# Power.net
KiCad netlist of a schematic drawn in Altium Designer
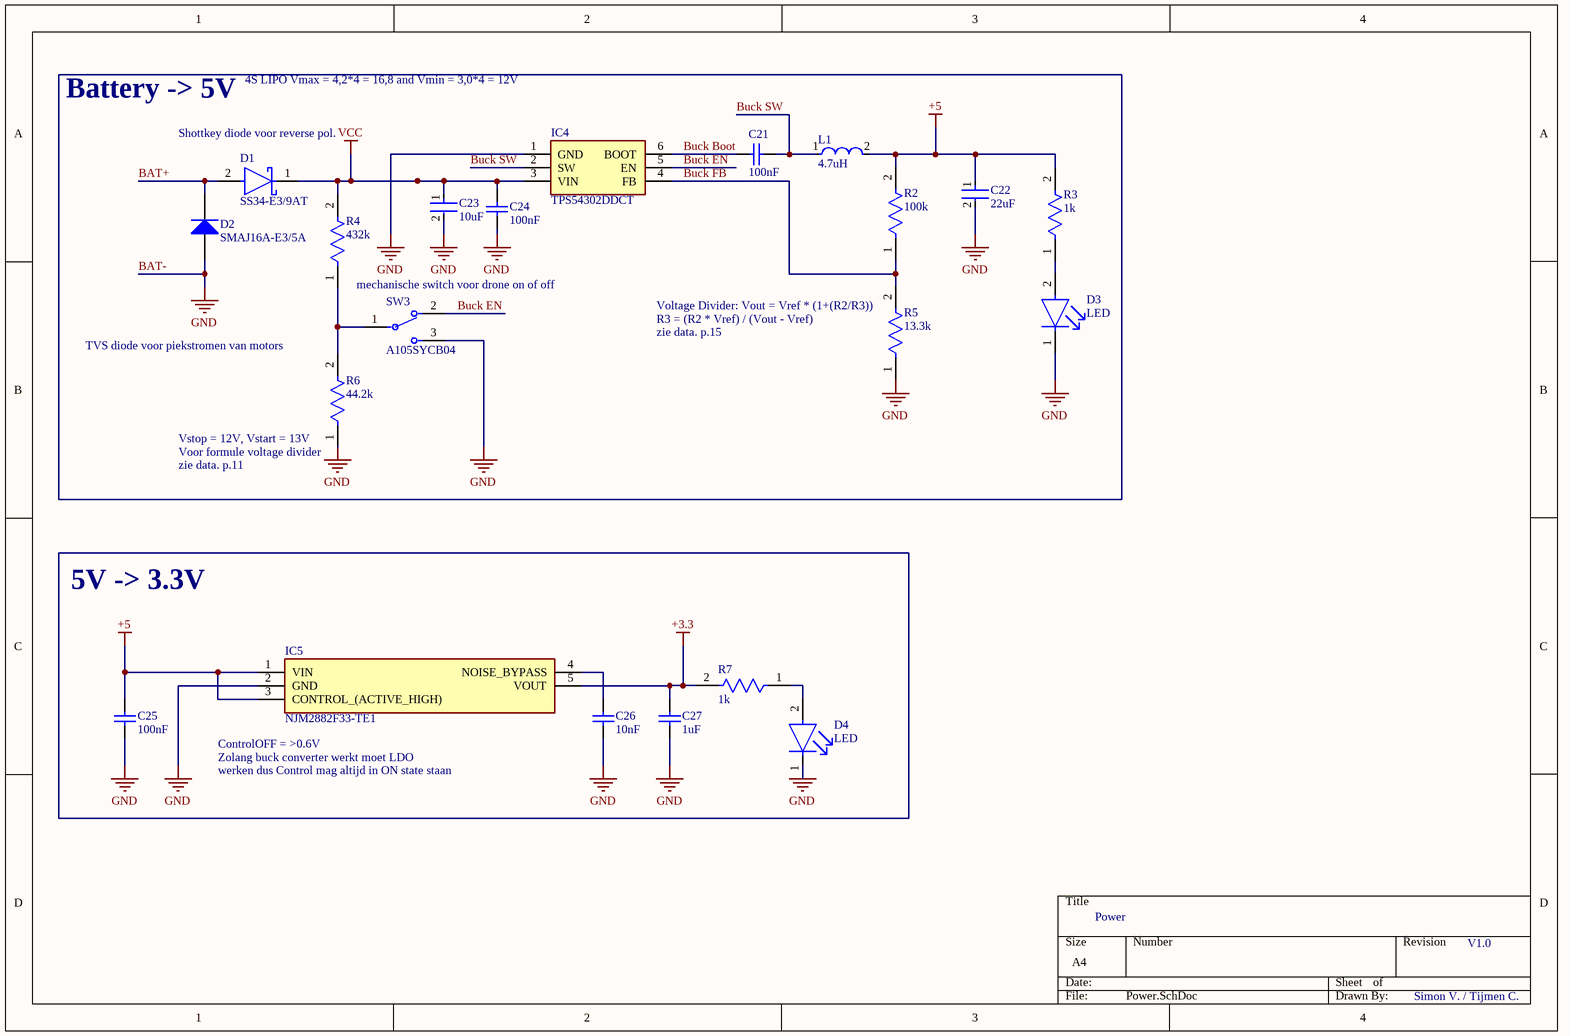
[diagram p0: Power.SchDoc]

(export (version "E")
  (design (tool "Eeschema 10.0.6"))
  (components
    (comp (ref "C21")
      (value "100nF")
      (footprint "CAPC1608X92X38ML15T08")
      (fields (field (name "PART NUMBER") "VJ0603Y104MXXAC") (field (name "MANUFACTURER") "Vitramon"))
      (libsource (lib "Altium Content Vault") (part "CAP"))
    )
    (comp (ref "C22")
      (value "22uF")
      (footprint "FP-GRM188-0_2-IPC_A")
      (description "Multilayer Ceramic Capacitor 22uF 20% 16V X5R 0603 Paper T/R")
      (libsource (lib "Altium Content Vault") (part "02cd4be3c70576c341d710602a673aa"))
    )
    (comp (ref "C23")
      (value "10uF")
      (footprint "FP-ZRB18AR61E106ME01L-MFG")
      (description "CAP CER 10UF 25V X5R 0603")
      (fields (field (name "VOLTAGE") "25V") (field (name "TOLERANCE") "20%"))
      (libsource (lib "Altium Content Vault") (part "b4654b650e69147ec39a6b967a45e02"))
    )
    (comp (ref "C24")
      (value "100nF")
      (footprint "CAPC1608X92X38ML15T08")
      (fields (field (name "PART NUMBER") "VJ0603Y104MXXAC") (field (name "MANUFACTURER") "Vitramon"))
      (libsource (lib "Altium Content Vault") (part "CAP"))
    )
    (comp (ref "C25")
      (value "100nF")
      (footprint "CAPC1608X92X38ML15T08")
      (fields (field (name "PART NUMBER") "VJ0603Y104MXXAC") (field (name "MANUFACTURER") "Vitramon"))
      (libsource (lib "Altium Content Vault") (part "CAP"))
    )
    (comp (ref "C26")
      (value "10nF")
      (footprint "CAPC1608X92X38LL15T08")
      (fields (field (name "MANUFACTURER") "Vitramon") (field (name "PART NUMBER") "VJ0603Y103JXXAC"))
      (libsource (lib "Altium Content Vault") (part "CAP"))
    )
    (comp (ref "C27")
      (value "1uF")
      (footprint "CAPC1608X90X35NL15T15")
      (fields
        (field (name "PART NUMBER") "0603YD105MAT2A")
        (field (name "MANUFACTURER") "AVX Interconnect / Elco")
      )
      (libsource (lib "Altium Content Vault") (part "CAP"))
    )
    (comp (ref "D1")
      (value "SS34-E3/9AT")
      (footprint "FP-SMC-MFG")
      (description "DIODE SCHOTTKY 40V 3A DO214AB")
      (libsource (lib "Altium Content Vault") (part "c1678fac7984e62e0809fbf79c06691"))
    )
    (comp (ref "D2")
      (value "SMAJ16A-E3/5A")
      (footprint "VISH-DO-214AC-2_M")
      (fields (field (name "MANUFACTURER") "Vishay Semiconductor"))
      (libsource (lib "Altium Content Vault") (part "VISH-K1A2-2"))
    )
    (comp (ref "D3")
      (value "LED")
      (footprint "FP-APHD1608LZGCK-MFG")
      (description "LED GREEN CLEAR 1608 SMD, type: APHD1608LZGCK")
      (libsource (lib "Altium Content Vault") (part "8706943c75ba83719d021d2fdc84c58"))
    )
    (comp (ref "D4")
      (value "LED")
      (footprint "FP-APHD1608LZGCK-MFG")
      (description "LED GREEN CLEAR 1608 SMD, type: APHD1608LZGCK")
      (libsource (lib "Altium Content Vault") (part "8706943c75ba83719d021d2fdc84c58"))
    )
    (comp (ref "IC4")
      (value "TPS54302DDCT")
      (footprint "SamacSys:SOT95P280X110-6N")
      (description "Integrated Circuit")
      (fields (field (name "MOUSER PART NUMBER") "595-TPS54302DDCT"))
      (libsource (lib "*") (part "TPS54302DDCT"))
    )
    (comp (ref "IC5")
      (value "NJM2882F33-TE1")
      (footprint "SamacSys:SOT95P280X130-5N")
      (description "Integrated Circuit")
      (fields (field (name "MOUSER PART NUMBER") "513-NJM2882F33-TE1"))
      (libsource (lib "*") (part "NJM2882F33-TE1"))
    )
    (comp (ref "L1")
      (value "4.7uH")
      (footprint "FP-IHLP-2020BZ-FP_1_905x2-MFG")
      (description "Fixed Inductors Commercial High Saturation Series 4.7uH 2.8A 116.6mΩ 20%")
      (fields (field (name "TOLERANCE") "20%"))
      (libsource (lib "Altium Content Vault") (part "725321dda6339637d4d059423bc1c3c"))
    )
    (comp (ref "R2")
      (value "100k")
      (footprint "FP-SR0603-MFG")
      (description "RES SMD 0603 1/4W 1% 100K OHM")
      (fields
        (field (name "OCTOPART") "https://octopart.com/sr0603fr-7t100kl-yageo-91478071")
        (field (name "TOLERANCE") "0.01")
      )
      (libsource (lib "Altium Content Vault") (part "1029c3af85768c4190bb7ad29bc67b5"))
    )
    (comp (ref "R3")
      (value "1k")
      (footprint "FP-AC0603-IPC_B")
      (description "RES 1kΩ 1.00% 0.2W 0603")
      (libsource (lib "Altium Content Vault") (part "1029c3af85768c4190bb7ad29bc67b5"))
    )
    (comp (ref "R4")
      (value "432k")
      (footprint "FP-AC0603-MFG")
      (description "RES 432KΩ 1.00% 0.1W 0603")
      (fields (field (name "TOLERANCE") "1%"))
      (libsource (lib "Altium Content Vault") (part "1029c3af85768c4190bb7ad29bc67b5"))
    )
    (comp (ref "R5")
      (value "13.3k")
      (footprint "FP-AF0603-IPC_A")
      (description "Anti-Sulfurated Chip Resistors Automotive Grade 13.3kΩ 1% 100ppm/°C 0603")
      (fields (field (name "TOLERANCE") "1%"))
      (libsource (lib "Altium Content Vault") (part "1029c3af85768c4190bb7ad29bc67b5"))
    )
    (comp (ref "R6")
      (value "44.2k")
      (footprint "FP-CRCW0603-HPe3-IPC_A")
      (description "RES Thick Film, 44.2kΩ, 1%, 0.33W, 100ppm/°C, 0603")
      (fields (field (name "TOLERANCE") "1%"))
      (libsource (lib "Altium Content Vault") (part "1029c3af85768c4190bb7ad29bc67b5"))
    )
    (comp (ref "R7")
      (value "1k")
      (footprint "FP-AC0603-IPC_B")
      (description "RES 1kΩ 1.00% 0.2W 0603")
      (libsource (lib "Altium Content Vault") (part "1029c3af85768c4190bb7ad29bc67b5"))
    )
    (comp (ref "SW3")
      (value "A105SYCB04")
      (footprint "FP-A105SYCB04-MFG")
      (description "SWITCH TOGGLE SPDT 0.4VA 20V")
      (libsource (lib "Altium Content Vault") (part "edb4360d59316bed191fd4b931ffec7"))
    )
  )
  (nets
    (net (code "1") (name "+3.3") (class "Default")
      (node (ref "C27") (pin "2") (pinfunction "2_2") (pintype "passive"))
      (node (ref "IC5") (pin "5") (pinfunction "VOUT_5") (pintype "passive"))
      (node (ref "R7") (pin "2") (pinfunction "2_2") (pintype "passive"))
    )
    (net (code "2") (name "+5") (class "Default")
      (node (ref "C22") (pin "1") (pinfunction "1_1") (pintype "passive"))
      (node (ref "C25") (pin "2") (pinfunction "2_2") (pintype "passive"))
      (node (ref "IC5") (pin "1") (pinfunction "VIN_1") (pintype "passive"))
      (node (ref "IC5") (pin "3") (pinfunction "CONTROL_(ACTIVE_HIGH)_3") (pintype "passive"))
      (node (ref "L1") (pin "2") (pinfunction "2_2") (pintype "passive"))
      (node (ref "R2") (pin "2") (pinfunction "2_2") (pintype "passive"))
      (node (ref "R3") (pin "2") (pinfunction "2_2") (pintype "passive"))
    )
    (net (code "3") (name "/BAT+") (class "Default")
      (node (ref "D1") (pin "2") (pinfunction "A_2") (pintype "passive"))
      (node (ref "D2") (pin "1") (pinfunction "K_1") (pintype "passive"))
    )
    (net (code "4") (name "/Buck Boot") (class "Default")
      (node (ref "C21") (pin "2") (pinfunction "2_2") (pintype "passive"))
      (node (ref "IC4") (pin "6") (pinfunction "BOOT_6") (pintype "passive"))
    )
    (net (code "5") (name "/Buck EN") (class "Default")
      (node (ref "IC4") (pin "5") (pinfunction "EN_5") (pintype "passive"))
      (node (ref "SW3") (pin "2") (pinfunction "2_2") (pintype "passive"))
    )
    (net (code "6") (name "/Buck FB") (class "Default")
      (node (ref "IC4") (pin "4") (pinfunction "FB_4") (pintype "passive"))
      (node (ref "R2") (pin "1") (pinfunction "1_1") (pintype "passive"))
      (node (ref "R5") (pin "2") (pinfunction "2_2") (pintype "passive"))
    )
    (net (code "7") (name "/Buck SW") (class "Default")
      (node (ref "C21") (pin "1") (pinfunction "1_1") (pintype "passive"))
      (node (ref "IC4") (pin "2") (pinfunction "SW_2") (pintype "passive"))
      (node (ref "L1") (pin "1") (pinfunction "1_1") (pintype "passive"))
    )
    (net (code "8") (name "GND") (class "Default")
      (node (ref "C22") (pin "2") (pinfunction "2_2") (pintype "passive"))
      (node (ref "C23") (pin "2") (pinfunction "2_2") (pintype "passive"))
      (node (ref "C24") (pin "1") (pinfunction "1_1") (pintype "passive"))
      (node (ref "C25") (pin "1") (pinfunction "1_1") (pintype "passive"))
      (node (ref "C26") (pin "1") (pinfunction "1_1") (pintype "passive"))
      (node (ref "C27") (pin "1") (pinfunction "1_1") (pintype "passive"))
      (node (ref "D2") (pin "2") (pinfunction "A_2") (pintype "passive"))
      (node (ref "D3") (pin "1") (pinfunction "C_1") (pintype "passive"))
      (node (ref "D4") (pin "1") (pinfunction "C_1") (pintype "passive"))
      (node (ref "IC4") (pin "1") (pinfunction "GND_1") (pintype "passive"))
      (node (ref "IC5") (pin "2") (pinfunction "GND_2") (pintype "passive"))
      (node (ref "R5") (pin "1") (pinfunction "1_1") (pintype "passive"))
      (node (ref "R6") (pin "1") (pinfunction "1_1") (pintype "passive"))
      (node (ref "SW3") (pin "3") (pinfunction "3_3") (pintype "passive"))
    )
    (net (code "9") (name "Net-(D3-A)") (class "Default")
      (node (ref "D3") (pin "2") (pinfunction "A_2") (pintype "passive"))
      (node (ref "R3") (pin "1") (pinfunction "1_1") (pintype "passive"))
    )
    (net (code "10") (name "Net-(D4-A)") (class "Default")
      (node (ref "D4") (pin "2") (pinfunction "A_2") (pintype "passive"))
      (node (ref "R7") (pin "1") (pinfunction "1_1") (pintype "passive"))
    )
    (net (code "11") (name "Net-(IC5-NOISE_BYPASS)") (class "Default")
      (node (ref "C26") (pin "2") (pinfunction "2_2") (pintype "passive"))
      (node (ref "IC5") (pin "4") (pinfunction "NOISE_BYPASS_4") (pintype "passive"))
    )
    (net (code "12") (name "Net-(R4-Pad1)") (class "Default")
      (node (ref "R4") (pin "1") (pinfunction "1_1") (pintype "passive"))
      (node (ref "R6") (pin "2") (pinfunction "2_2") (pintype "passive"))
      (node (ref "SW3") (pin "1") (pinfunction "1_1") (pintype "passive"))
    )
    (net (code "13") (name "VCC") (class "Default")
      (node (ref "C23") (pin "1") (pinfunction "1_1") (pintype "passive"))
      (node (ref "C24") (pin "2") (pinfunction "2_2") (pintype "passive"))
      (node (ref "D1") (pin "1") (pinfunction "C_1") (pintype "passive"))
      (node (ref "IC4") (pin "3") (pinfunction "VIN_3") (pintype "passive"))
      (node (ref "R4") (pin "2") (pinfunction "2_2") (pintype "passive"))
    )
  )
)
